# Microcontroller.net
KiCad netlist of a schematic drawn in Altium Designer
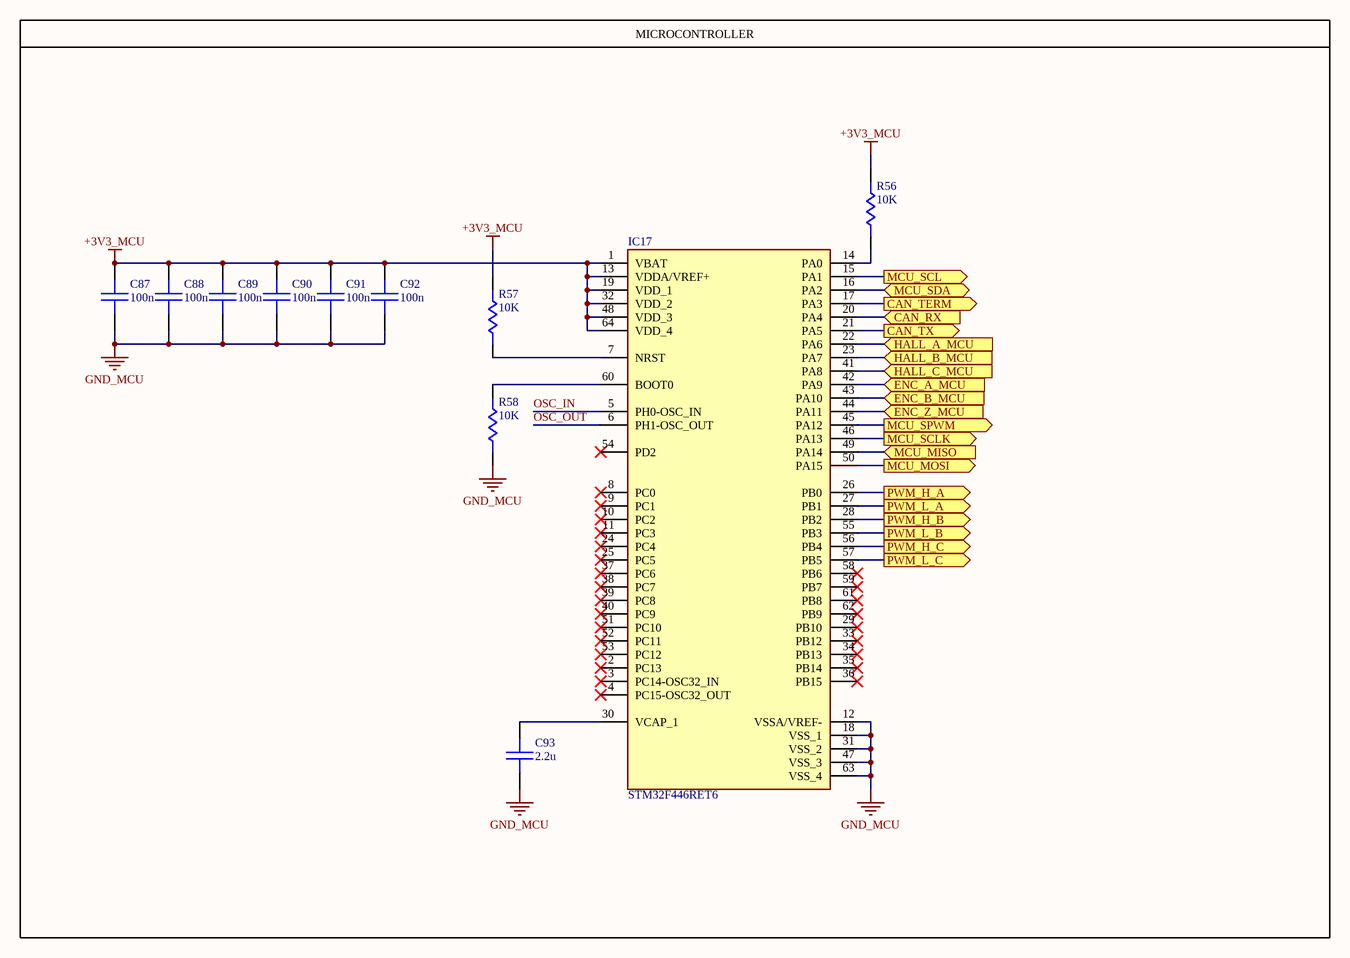
[diagram p0: Microcontroller.SchDoc]

(export (version "E")
  (design (tool "Eeschema 10.0.6"))
  (components
    (comp (ref "C87")
      (value "100n")
      (footprint "C_0603")
      (description "SMD Chip Capacitor")
      (libsource (lib "My_Integrated_Lib") (part "CAP"))
    )
    (comp (ref "C88")
      (value "100n")
      (footprint "C_0603")
      (description "SMD Chip Capacitor")
      (libsource (lib "My_Integrated_Lib") (part "CAP"))
    )
    (comp (ref "C89")
      (value "100n")
      (footprint "C_0603")
      (description "SMD Chip Capacitor")
      (libsource (lib "My_Integrated_Lib") (part "CAP"))
    )
    (comp (ref "C90")
      (value "100n")
      (footprint "C_0603")
      (description "SMD Chip Capacitor")
      (libsource (lib "My_Integrated_Lib") (part "CAP"))
    )
    (comp (ref "C91")
      (value "100n")
      (footprint "C_0603")
      (description "SMD Chip Capacitor")
      (libsource (lib "My_Integrated_Lib") (part "CAP"))
    )
    (comp (ref "C92")
      (value "100n")
      (footprint "C_0603")
      (description "SMD Chip Capacitor")
      (libsource (lib "My_Integrated_Lib") (part "CAP"))
    )
    (comp (ref "C93")
      (value "2.2u")
      (footprint "C_0603")
      (description "SMD Chip Capacitor")
      (libsource (lib "My_Integrated_Lib") (part "CAP"))
    )
    (comp (ref "IC17")
      (value "STM32F446RET6")
      (footprint "QFP50P1200X1200X160-64N")
      (description "Integrated Circuit")
      (fields (field (name "MOUSER PART NUMBER") "511-STM32F446RET6"))
      (libsource (lib "My_Integrated_Lib") (part "STM32F446RET6"))
    )
    (comp (ref "R56")
      (value "10K")
      (footprint "R_0603")
      (description "SMD Chip Resistor")
      (libsource (lib "My_Integrated_Lib") (part "RES"))
    )
    (comp (ref "R57")
      (value "10K")
      (footprint "R_0603")
      (description "SMD Chip Resistor")
      (libsource (lib "My_Integrated_Lib") (part "RES"))
    )
    (comp (ref "R58")
      (value "10K")
      (footprint "R_0603")
      (description "SMD Chip Resistor")
      (libsource (lib "My_Integrated_Lib") (part "RES"))
    )
  )
  (nets
    (net (code "1") (name "+3V3_MCU") (class "Default")
      (node (ref "C87") (pin "2") (pinfunction "2_2") (pintype "passive"))
      (node (ref "C88") (pin "2") (pinfunction "2_2") (pintype "passive"))
      (node (ref "C89") (pin "2") (pinfunction "2_2") (pintype "passive"))
      (node (ref "C90") (pin "2") (pinfunction "2_2") (pintype "passive"))
      (node (ref "C91") (pin "2") (pinfunction "2_2") (pintype "passive"))
      (node (ref "C92") (pin "2") (pinfunction "2_2") (pintype "passive"))
      (node (ref "IC17") (pin "1") (pinfunction "VBAT_1") (pintype "passive"))
      (node (ref "IC17") (pin "13") (pinfunction "VDDA/VREF+_13") (pintype "passive"))
      (node (ref "IC17") (pin "19") (pinfunction "VDD_1_19") (pintype "passive"))
      (node (ref "IC17") (pin "32") (pinfunction "VDD_2_32") (pintype "passive"))
      (node (ref "IC17") (pin "48") (pinfunction "VDD_3_48") (pintype "passive"))
      (node (ref "IC17") (pin "64") (pinfunction "VDD_4_64") (pintype "passive"))
      (node (ref "R56") (pin "1") (pinfunction "1_1") (pintype "passive"))
      (node (ref "R57") (pin "1") (pinfunction "1_1") (pintype "passive"))
    )
    (net (code "2") (name "/CAN_RX") (class "Default")
      (node (ref "IC17") (pin "20") (pinfunction "PA4_20") (pintype "passive"))
    )
    (net (code "3") (name "/CAN_TERM") (class "Default")
      (node (ref "IC17") (pin "17") (pinfunction "PA3_17") (pintype "passive"))
    )
    (net (code "4") (name "/CAN_TX") (class "Default")
      (node (ref "IC17") (pin "21") (pinfunction "PA5_21") (pintype "passive"))
    )
    (net (code "5") (name "/ENC_A_MCU") (class "Default")
      (node (ref "IC17") (pin "42") (pinfunction "PA9_42") (pintype "passive"))
    )
    (net (code "6") (name "/ENC_B_MCU") (class "Default")
      (node (ref "IC17") (pin "43") (pinfunction "PA10_43") (pintype "passive"))
    )
    (net (code "7") (name "/ENC_Z_MCU") (class "Default")
      (node (ref "IC17") (pin "44") (pinfunction "PA11_44") (pintype "passive"))
    )
    (net (code "8") (name "/HALL_A_MCU") (class "Default")
      (node (ref "IC17") (pin "22") (pinfunction "PA6_22") (pintype "passive"))
    )
    (net (code "9") (name "/HALL_B_MCU") (class "Default")
      (node (ref "IC17") (pin "23") (pinfunction "PA7_23") (pintype "passive"))
    )
    (net (code "10") (name "/HALL_C_MCU") (class "Default")
      (node (ref "IC17") (pin "41") (pinfunction "PA8_41") (pintype "passive"))
    )
    (net (code "11") (name "/MCU_MISO") (class "Default")
      (node (ref "IC17") (pin "49") (pinfunction "PA14_49") (pintype "passive"))
    )
    (net (code "12") (name "/MCU_MOSI") (class "Default")
      (node (ref "IC17") (pin "50") (pinfunction "PA15_50") (pintype "passive"))
    )
    (net (code "13") (name "/MCU_SCL") (class "Default")
      (node (ref "IC17") (pin "15") (pinfunction "PA1_15") (pintype "passive"))
    )
    (net (code "14") (name "/MCU_SCLK") (class "Default")
      (node (ref "IC17") (pin "46") (pinfunction "PA13_46") (pintype "passive"))
    )
    (net (code "15") (name "/MCU_SDA") (class "Default")
      (node (ref "IC17") (pin "16") (pinfunction "PA2_16") (pintype "passive"))
    )
    (net (code "16") (name "/MCU_SPWM") (class "Default")
      (node (ref "IC17") (pin "45") (pinfunction "PA12_45") (pintype "passive"))
    )
    (net (code "17") (name "/OSC_IN") (class "Default")
      (node (ref "IC17") (pin "5") (pinfunction "PH0-OSC_IN_5") (pintype "passive"))
    )
    (net (code "18") (name "/OSC_OUT") (class "Default")
      (node (ref "IC17") (pin "6") (pinfunction "PH1-OSC_OUT_6") (pintype "passive"))
    )
    (net (code "19") (name "/PWM_H_A") (class "Default")
      (node (ref "IC17") (pin "26") (pinfunction "PB0_26") (pintype "passive"))
    )
    (net (code "20") (name "/PWM_H_B") (class "Default")
      (node (ref "IC17") (pin "28") (pinfunction "PB2_28") (pintype "passive"))
    )
    (net (code "21") (name "/PWM_H_C") (class "Default")
      (node (ref "IC17") (pin "56") (pinfunction "PB4_56") (pintype "passive"))
    )
    (net (code "22") (name "/PWM_L_A") (class "Default")
      (node (ref "IC17") (pin "27") (pinfunction "PB1_27") (pintype "passive"))
    )
    (net (code "23") (name "/PWM_L_B") (class "Default")
      (node (ref "IC17") (pin "55") (pinfunction "PB3_55") (pintype "passive"))
    )
    (net (code "24") (name "/PWM_L_C") (class "Default")
      (node (ref "IC17") (pin "57") (pinfunction "PB5_57") (pintype "passive"))
    )
    (net (code "25") (name "GND_MCU") (class "Default")
      (node (ref "C87") (pin "1") (pinfunction "1_1") (pintype "passive"))
      (node (ref "C88") (pin "1") (pinfunction "1_1") (pintype "passive"))
      (node (ref "C89") (pin "1") (pinfunction "1_1") (pintype "passive"))
      (node (ref "C90") (pin "1") (pinfunction "1_1") (pintype "passive"))
      (node (ref "C91") (pin "1") (pinfunction "1_1") (pintype "passive"))
      (node (ref "C92") (pin "1") (pinfunction "1_1") (pintype "passive"))
      (node (ref "C93") (pin "1") (pinfunction "1_1") (pintype "passive"))
      (node (ref "IC17") (pin "12") (pinfunction "VSSA/VREF-_12") (pintype "passive"))
      (node (ref "IC17") (pin "18") (pinfunction "VSS_1_18") (pintype "passive"))
      (node (ref "IC17") (pin "31") (pinfunction "VSS_2_31") (pintype "passive"))
      (node (ref "IC17") (pin "47") (pinfunction "VSS_3_47") (pintype "passive"))
      (node (ref "IC17") (pin "63") (pinfunction "VSS_4_63") (pintype "passive"))
      (node (ref "R58") (pin "2") (pinfunction "2_2") (pintype "passive"))
    )
    (net (code "26") (name "Net-(IC17-BOOT0)") (class "Default")
      (node (ref "IC17") (pin "60") (pinfunction "BOOT0_60") (pintype "passive"))
      (node (ref "R58") (pin "1") (pinfunction "1_1") (pintype "passive"))
    )
    (net (code "27") (name "Net-(IC17-NRST)") (class "Default")
      (node (ref "IC17") (pin "7") (pinfunction "NRST_7") (pintype "passive"))
      (node (ref "R57") (pin "2") (pinfunction "2_2") (pintype "passive"))
    )
    (net (code "28") (name "Net-(IC17-PA0)") (class "Default")
      (node (ref "IC17") (pin "14") (pinfunction "PA0_14") (pintype "passive"))
      (node (ref "R56") (pin "2") (pinfunction "2_2") (pintype "passive"))
    )
    (net (code "29") (name "Net-(IC17-VCAP_1)") (class "Default")
      (node (ref "C93") (pin "2") (pinfunction "2_2") (pintype "passive"))
      (node (ref "IC17") (pin "30") (pinfunction "VCAP_1_30") (pintype "passive"))
    )
    (net (code "30") (name "unconnected-(IC17-PB6-Pad58)") (class "Default")
      (node (ref "IC17") (pin "58") (pinfunction "PB6_58") (pintype "passive+no_connect"))
    )
    (net (code "31") (name "unconnected-(IC17-PB7-Pad59)") (class "Default")
      (node (ref "IC17") (pin "59") (pinfunction "PB7_59") (pintype "passive+no_connect"))
    )
    (net (code "32") (name "unconnected-(IC17-PB8-Pad61)") (class "Default")
      (node (ref "IC17") (pin "61") (pinfunction "PB8_61") (pintype "passive+no_connect"))
    )
    (net (code "33") (name "unconnected-(IC17-PB9-Pad62)") (class "Default")
      (node (ref "IC17") (pin "62") (pinfunction "PB9_62") (pintype "passive+no_connect"))
    )
    (net (code "34") (name "unconnected-(IC17-PB10-Pad29)") (class "Default")
      (node (ref "IC17") (pin "29") (pinfunction "PB10_29") (pintype "passive+no_connect"))
    )
    (net (code "35") (name "unconnected-(IC17-PB12-Pad33)") (class "Default")
      (node (ref "IC17") (pin "33") (pinfunction "PB12_33") (pintype "passive+no_connect"))
    )
    (net (code "36") (name "unconnected-(IC17-PB13-Pad34)") (class "Default")
      (node (ref "IC17") (pin "34") (pinfunction "PB13_34") (pintype "passive+no_connect"))
    )
    (net (code "37") (name "unconnected-(IC17-PB14-Pad35)") (class "Default")
      (node (ref "IC17") (pin "35") (pinfunction "PB14_35") (pintype "passive+no_connect"))
    )
    (net (code "38") (name "unconnected-(IC17-PB15-Pad36)") (class "Default")
      (node (ref "IC17") (pin "36") (pinfunction "PB15_36") (pintype "passive+no_connect"))
    )
    (net (code "39") (name "unconnected-(IC17-PC0-Pad8)") (class "Default")
      (node (ref "IC17") (pin "8") (pinfunction "PC0_8") (pintype "passive+no_connect"))
    )
    (net (code "40") (name "unconnected-(IC17-PC1-Pad9)") (class "Default")
      (node (ref "IC17") (pin "9") (pinfunction "PC1_9") (pintype "passive+no_connect"))
    )
    (net (code "41") (name "unconnected-(IC17-PC2-Pad10)") (class "Default")
      (node (ref "IC17") (pin "10") (pinfunction "PC2_10") (pintype "passive+no_connect"))
    )
    (net (code "42") (name "unconnected-(IC17-PC3-Pad11)") (class "Default")
      (node (ref "IC17") (pin "11") (pinfunction "PC3_11") (pintype "passive+no_connect"))
    )
    (net (code "43") (name "unconnected-(IC17-PC4-Pad24)") (class "Default")
      (node (ref "IC17") (pin "24") (pinfunction "PC4_24") (pintype "passive+no_connect"))
    )
    (net (code "44") (name "unconnected-(IC17-PC5-Pad25)") (class "Default")
      (node (ref "IC17") (pin "25") (pinfunction "PC5_25") (pintype "passive+no_connect"))
    )
    (net (code "45") (name "unconnected-(IC17-PC6-Pad37)") (class "Default")
      (node (ref "IC17") (pin "37") (pinfunction "PC6_37") (pintype "passive+no_connect"))
    )
    (net (code "46") (name "unconnected-(IC17-PC7-Pad38)") (class "Default")
      (node (ref "IC17") (pin "38") (pinfunction "PC7_38") (pintype "passive+no_connect"))
    )
    (net (code "47") (name "unconnected-(IC17-PC8-Pad39)") (class "Default")
      (node (ref "IC17") (pin "39") (pinfunction "PC8_39") (pintype "passive+no_connect"))
    )
    (net (code "48") (name "unconnected-(IC17-PC9-Pad40)") (class "Default")
      (node (ref "IC17") (pin "40") (pinfunction "PC9_40") (pintype "passive+no_connect"))
    )
    (net (code "49") (name "unconnected-(IC17-PC10-Pad51)") (class "Default")
      (node (ref "IC17") (pin "51") (pinfunction "PC10_51") (pintype "passive+no_connect"))
    )
    (net (code "50") (name "unconnected-(IC17-PC11-Pad52)") (class "Default")
      (node (ref "IC17") (pin "52") (pinfunction "PC11_52") (pintype "passive+no_connect"))
    )
    (net (code "51") (name "unconnected-(IC17-PC12-Pad53)") (class "Default")
      (node (ref "IC17") (pin "53") (pinfunction "PC12_53") (pintype "passive+no_connect"))
    )
    (net (code "52") (name "unconnected-(IC17-PC13-Pad2)") (class "Default")
      (node (ref "IC17") (pin "2") (pinfunction "PC13_2") (pintype "passive+no_connect"))
    )
    (net (code "53") (name "unconnected-(IC17-PC14-OSC32_IN-Pad3)") (class "Default")
      (node (ref "IC17") (pin "3") (pinfunction "PC14-OSC32_IN_3") (pintype "passive+no_connect"))
    )
    (net (code "54") (name "unconnected-(IC17-PC15-OSC32_OUT-Pad4)") (class "Default")
      (node (ref "IC17") (pin "4") (pinfunction "PC15-OSC32_OUT_4") (pintype "passive+no_connect"))
    )
    (net (code "55") (name "unconnected-(IC17-PD2-Pad54)") (class "Default")
      (node (ref "IC17") (pin "54") (pinfunction "PD2_54") (pintype "passive+no_connect"))
    )
  )
)
